# schema2.net
KiCad netlist of a schematic drawn in Altium Designer
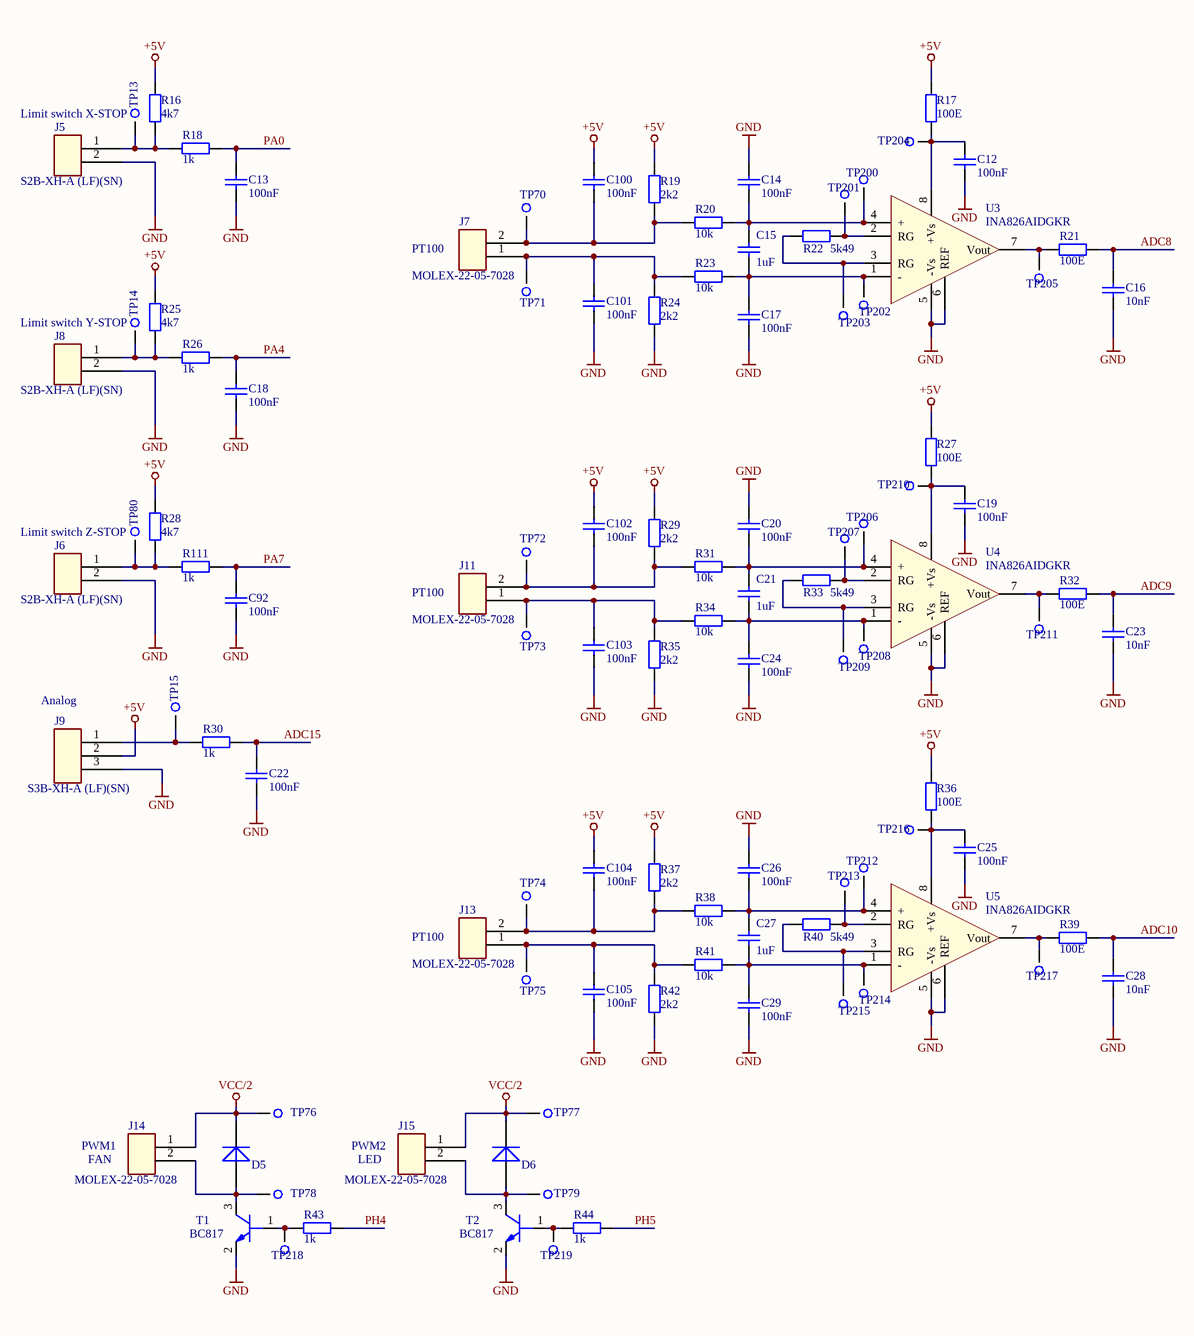
[diagram p0: schema2.SchDoc]

(export (version "E")
  (design (tool "Eeschema 10.0.6"))
  (components
    (comp (ref "C12")
      (value "100nF")
      (footprint "C0603")
      (description "RO X7R 100nF 10% 50V 0603")
      (libsource (lib "Database_Faber") (part "Capacitor"))
    )
    (comp (ref "C13")
      (value "100nF")
      (footprint "C0603")
      (description "RO X7R 100nF 10% 50V 0603")
      (libsource (lib "Database_Faber") (part "Capacitor"))
    )
    (comp (ref "C14")
      (value "100nF")
      (footprint "C0603")
      (description "RO X7R 100nF 10% 50V 0603")
      (libsource (lib "Database_Faber") (part "Capacitor"))
    )
    (comp (ref "C15")
      (value "1uF")
      (footprint "C0603")
      (description "RO X5R 1uF 10% 10V 0603")
      (libsource (lib "Database_Faber") (part "Capacitor"))
    )
    (comp (ref "C16")
      (value "10nF")
      (footprint "C0603")
      (description "RO X7R 10nF 10% 50V 0603")
      (libsource (lib "Database_Faber") (part "Capacitor"))
    )
    (comp (ref "C17")
      (value "100nF")
      (footprint "C0603")
      (description "RO X7R 100nF 10% 50V 0603")
      (libsource (lib "Database_Faber") (part "Capacitor"))
    )
    (comp (ref "C18")
      (value "100nF")
      (footprint "C0603")
      (description "RO X7R 100nF 10% 50V 0603")
      (libsource (lib "Database_Faber") (part "Capacitor"))
    )
    (comp (ref "C19")
      (value "100nF")
      (footprint "C0603")
      (description "RO X7R 100nF 10% 50V 0603")
      (libsource (lib "Database_Faber") (part "Capacitor"))
    )
    (comp (ref "C20")
      (value "100nF")
      (footprint "C0603")
      (description "RO X7R 100nF 10% 50V 0603")
      (libsource (lib "Database_Faber") (part "Capacitor"))
    )
    (comp (ref "C21")
      (value "1uF")
      (footprint "C0603")
      (description "RO X5R 1uF 10% 10V 0603")
      (libsource (lib "Database_Faber") (part "Capacitor"))
    )
    (comp (ref "C22")
      (value "100nF")
      (footprint "C0603")
      (description "RO X7R 100nF 10% 50V 0603")
      (libsource (lib "Database_Faber") (part "Capacitor"))
    )
    (comp (ref "C23")
      (value "10nF")
      (footprint "C0603")
      (description "RO X7R 10nF 10% 50V 0603")
      (libsource (lib "Database_Faber") (part "Capacitor"))
    )
    (comp (ref "C24")
      (value "100nF")
      (footprint "C0603")
      (description "RO X7R 100nF 10% 50V 0603")
      (libsource (lib "Database_Faber") (part "Capacitor"))
    )
    (comp (ref "C25")
      (value "100nF")
      (footprint "C0603")
      (description "RO X7R 100nF 10% 50V 0603")
      (libsource (lib "Database_Faber") (part "Capacitor"))
    )
    (comp (ref "C26")
      (value "100nF")
      (footprint "C0603")
      (description "RO X7R 100nF 10% 50V 0603")
      (libsource (lib "Database_Faber") (part "Capacitor"))
    )
    (comp (ref "C27")
      (value "1uF")
      (footprint "C0603")
      (description "RO X5R 1uF 10% 10V 0603")
      (libsource (lib "Database_Faber") (part "Capacitor"))
    )
    (comp (ref "C28")
      (value "10nF")
      (footprint "C0603")
      (description "RO X7R 10nF 10% 50V 0603")
      (libsource (lib "Database_Faber") (part "Capacitor"))
    )
    (comp (ref "C29")
      (value "100nF")
      (footprint "C0603")
      (description "RO X7R 100nF 10% 50V 0603")
      (libsource (lib "Database_Faber") (part "Capacitor"))
    )
    (comp (ref "C92")
      (value "100nF")
      (footprint "C0603")
      (description "RO X7R 100nF 10% 50V 0603")
      (libsource (lib "Database_Faber") (part "Capacitor"))
    )
    (comp (ref "C100")
      (value "100nF")
      (footprint "C0603")
      (description "RO X7R 100nF 10% 50V 0603")
      (libsource (lib "Database_Faber") (part "Capacitor"))
    )
    (comp (ref "C101")
      (value "100nF")
      (footprint "C0603")
      (description "RO X7R 100nF 10% 50V 0603")
      (libsource (lib "Database_Faber") (part "Capacitor"))
    )
    (comp (ref "C102")
      (value "100nF")
      (footprint "C0603")
      (description "RO X7R 100nF 10% 50V 0603")
      (libsource (lib "Database_Faber") (part "Capacitor"))
    )
    (comp (ref "C103")
      (value "100nF")
      (footprint "C0603")
      (description "RO X7R 100nF 10% 50V 0603")
      (libsource (lib "Database_Faber") (part "Capacitor"))
    )
    (comp (ref "C104")
      (value "100nF")
      (footprint "C0603")
      (description "RO X7R 100nF 10% 50V 0603")
      (libsource (lib "Database_Faber") (part "Capacitor"))
    )
    (comp (ref "C105")
      (value "100nF")
      (footprint "C0603")
      (description "RO X7R 100nF 10% 50V 0603")
      (libsource (lib "Database_Faber") (part "Capacitor"))
    )
    (comp (ref "D5")
      (value "S1G")
      (footprint "DO214AC (SMA)")
      (description "RO DIODE S1G DO-214AC")
      (libsource (lib "Database_Faber") (part "Diode"))
    )
    (comp (ref "D6")
      (value "S1G")
      (footprint "DO214AC (SMA)")
      (description "RO DIODE S1G DO-214AC")
      (libsource (lib "Database_Faber") (part "Diode"))
    )
    (comp (ref "J5")
      (value "S2B-XH-A (LF)(SN)")
      (footprint "S2B-XH-A (LF)(SN)")
      (description "RO CONN PR 2p HKS S2B-XH-A (LF)(SN) JST")
      (fields (field (name "MFG") "JST (JAPAN SOLDERLESS TERMINALS)"))
      (libsource (lib "Database_Faber") (part "HEADER 2"))
    )
    (comp (ref "J6")
      (value "S2B-XH-A (LF)(SN)")
      (footprint "S2B-XH-A (LF)(SN)")
      (description "RO CONN PR 2p HKS S2B-XH-A (LF)(SN) JST")
      (fields (field (name "MFG") "JST (JAPAN SOLDERLESS TERMINALS)"))
      (libsource (lib "Database_Faber") (part "HEADER 2"))
    )
    (comp (ref "J7")
      (value "MOLEX-22-05-7028")
      (footprint "MOLEX-22-05-7028")
      (description "RO CONN PR 2p HKS 22-05-7028 MOLEX")
      (fields (field (name "MFG") "MOLEX"))
      (libsource (lib "") (part "HEADER 2_1"))
    )
    (comp (ref "J8")
      (value "S2B-XH-A (LF)(SN)")
      (footprint "S2B-XH-A (LF)(SN)")
      (description "RO CONN PR 2p HKS S2B-XH-A (LF)(SN) JST")
      (fields (field (name "MFG") "JST (JAPAN SOLDERLESS TERMINALS)"))
      (libsource (lib "Database_Faber") (part "HEADER 2"))
    )
    (comp (ref "J9")
      (value "S3B-XH-A (LF)(SN)")
      (footprint "S3B-XH-A (LF)(SN)")
      (description "RO CONN PR 3p HKS S3B-XH-A (LF)(SN) JST")
      (fields (field (name "MFG") "JST (JAPAN SOLDERLESS TERMINALS)"))
      (libsource (lib "Database_Faber") (part "HEADER 3"))
    )
    (comp (ref "J11")
      (value "MOLEX-22-05-7028")
      (footprint "MOLEX-22-05-7028")
      (description "RO CONN PR 2p HKS 22-05-7028 MOLEX")
      (fields (field (name "MFG") "MOLEX"))
      (libsource (lib "") (part "HEADER 2_1"))
    )
    (comp (ref "J13")
      (value "MOLEX-22-05-7028")
      (footprint "MOLEX-22-05-7028")
      (description "RO CONN PR 2p HKS 22-05-7028 MOLEX")
      (fields (field (name "MFG") "MOLEX"))
      (libsource (lib "") (part "HEADER 2_1"))
    )
    (comp (ref "J14")
      (value "MOLEX-22-05-7028")
      (footprint "MOLEX-22-05-7028")
      (description "RO CONN PR 2p HKS 22-05-7028 MOLEX")
      (fields (field (name "MFG") "MOLEX"))
      (libsource (lib "Database_Faber") (part "HEADER 2"))
    )
    (comp (ref "J15")
      (value "MOLEX-22-05-7028")
      (footprint "MOLEX-22-05-7028")
      (description "RO CONN PR 2p HKS 22-05-7028 MOLEX")
      (fields (field (name "MFG") "MOLEX"))
      (libsource (lib "Database_Faber") (part "HEADER 2"))
    )
    (comp (ref "R16")
      (value "4k7")
      (footprint "R0603")
      (description "RO RES 4k70 1% 0,063W  0603")
      (libsource (lib "") (part "Resistor_2"))
    )
    (comp (ref "R17")
      (value "100E")
      (footprint "R0603")
      (description "RO RES 100E 1% 0,063W  0603")
      (libsource (lib "") (part "Resistor_1"))
    )
    (comp (ref "R18")
      (value "1k")
      (footprint "R0603")
      (description "RO RES 1k0 1% 0,1W  0603")
      (libsource (lib "Database_Faber") (part "Resistor"))
    )
    (comp (ref "R19")
      (value "2k2")
      (footprint "R0603")
      (description "RO RES 2k2 0,1% 0,063W 25ppm 0603")
      (fields (field (name "MFG") "TE CONNECTIVITY / NEOHM"))
      (libsource (lib "") (part "Resistor_1"))
    )
    (comp (ref "R20")
      (value "10k")
      (footprint "R0603")
      (description "RO RES 10k0 1% 0,063W  0603")
      (libsource (lib "Database_Faber") (part "Resistor"))
    )
    (comp (ref "R21")
      (value "100E")
      (footprint "R0603")
      (description "RO RES 100E 1% 0,063W  0603")
      (libsource (lib "Database_Faber") (part "Resistor"))
    )
    (comp (ref "R22")
      (value "5k49")
      (footprint "R0603")
      (description "RO RES 5K49 0,1% 0,063W 25ppm 0603")
      (fields (field (name "MFG") "WELWYN"))
      (libsource (lib "") (part "Resistor_3"))
    )
    (comp (ref "R23")
      (value "10k")
      (footprint "R0603")
      (description "RO RES 10k0 1% 0,063W  0603")
      (libsource (lib "Database_Faber") (part "Resistor"))
    )
    (comp (ref "R24")
      (value "2k2")
      (footprint "R0603")
      (description "RO RES 2k2 0,1% 0,063W 25ppm 0603")
      (fields (field (name "MFG") "TE CONNECTIVITY / NEOHM"))
      (libsource (lib "") (part "Resistor_2"))
    )
    (comp (ref "R25")
      (value "4k7")
      (footprint "R0603")
      (description "RO RES 4k70 1% 0,063W  0603")
      (libsource (lib "") (part "Resistor_2"))
    )
    (comp (ref "R26")
      (value "1k")
      (footprint "R0603")
      (description "RO RES 1k0 1% 0,1W  0603")
      (libsource (lib "Database_Faber") (part "Resistor"))
    )
    (comp (ref "R27")
      (value "100E")
      (footprint "R0603")
      (description "RO RES 100E 1% 0,063W  0603")
      (libsource (lib "") (part "Resistor_1"))
    )
    (comp (ref "R28")
      (value "4k7")
      (footprint "R0603")
      (description "RO RES 4k70 1% 0,063W  0603")
      (libsource (lib "") (part "Resistor_2"))
    )
    (comp (ref "R29")
      (value "2k2")
      (footprint "R0603")
      (description "RO RES 2k2 0,1% 0,063W 25ppm 0603")
      (fields (field (name "MFG") "TE CONNECTIVITY / NEOHM"))
      (libsource (lib "") (part "Resistor_1"))
    )
    (comp (ref "R30")
      (value "1k")
      (footprint "R0603")
      (description "RO RES 1k0 1% 0,1W  0603")
      (libsource (lib "Database_Faber") (part "Resistor"))
    )
    (comp (ref "R31")
      (value "10k")
      (footprint "R0603")
      (description "RO RES 10k0 1% 0,063W  0603")
      (libsource (lib "Database_Faber") (part "Resistor"))
    )
    (comp (ref "R32")
      (value "100E")
      (footprint "R0603")
      (description "RO RES 100E 1% 0,063W  0603")
      (libsource (lib "Database_Faber") (part "Resistor"))
    )
    (comp (ref "R33")
      (value "5k49")
      (footprint "R0603")
      (description "RO RES 5K49 0,1% 0,063W 25ppm 0603")
      (fields (field (name "MFG") "WELWYN"))
      (libsource (lib "") (part "Resistor_3"))
    )
    (comp (ref "R34")
      (value "10k")
      (footprint "R0603")
      (description "RO RES 10k0 1% 0,063W  0603")
      (libsource (lib "Database_Faber") (part "Resistor"))
    )
    (comp (ref "R35")
      (value "2k2")
      (footprint "R0603")
      (description "RO RES 2k2 0,1% 0,063W 25ppm 0603")
      (fields (field (name "MFG") "TE CONNECTIVITY / NEOHM"))
      (libsource (lib "") (part "Resistor_2"))
    )
    (comp (ref "R36")
      (value "100E")
      (footprint "R0603")
      (description "RO RES 100E 1% 0,063W  0603")
      (libsource (lib "") (part "Resistor_1"))
    )
    (comp (ref "R37")
      (value "2k2")
      (footprint "R0603")
      (description "RO RES 2k2 0,1% 0,063W 25ppm 0603")
      (fields (field (name "MFG") "TE CONNECTIVITY / NEOHM"))
      (libsource (lib "") (part "Resistor_1"))
    )
    (comp (ref "R38")
      (value "10k")
      (footprint "R0603")
      (description "RO RES 10k0 1% 0,063W  0603")
      (libsource (lib "Database_Faber") (part "Resistor"))
    )
    (comp (ref "R39")
      (value "100E")
      (footprint "R0603")
      (description "RO RES 100E 1% 0,063W  0603")
      (libsource (lib "Database_Faber") (part "Resistor"))
    )
    (comp (ref "R40")
      (value "5k49")
      (footprint "R0603")
      (description "RO RES 5K49 0,1% 0,063W 25ppm 0603")
      (fields (field (name "MFG") "WELWYN"))
      (libsource (lib "") (part "Resistor_3"))
    )
    (comp (ref "R41")
      (value "10k")
      (footprint "R0603")
      (description "RO RES 10k0 1% 0,063W  0603")
      (libsource (lib "Database_Faber") (part "Resistor"))
    )
    (comp (ref "R42")
      (value "2k2")
      (footprint "R0603")
      (description "RO RES 2k2 0,1% 0,063W 25ppm 0603")
      (fields (field (name "MFG") "TE CONNECTIVITY / NEOHM"))
      (libsource (lib "") (part "Resistor_2"))
    )
    (comp (ref "R43")
      (value "1k")
      (footprint "R0603")
      (description "RO RES 1k0 1% 0,1W  0603")
      (libsource (lib "") (part "Resistor_3"))
    )
    (comp (ref "R44")
      (value "1k")
      (footprint "R0603")
      (description "RO RES 1k0 1% 0,1W  0603")
      (libsource (lib "") (part "Resistor_3"))
    )
    (comp (ref "R111")
      (value "1k")
      (footprint "R0603")
      (description "RO RES 1k0 1% 0,1W  0603")
      (libsource (lib "Database_Faber") (part "Resistor"))
    )
    (comp (ref "T1")
      (value "BC817")
      (footprint "SOT23")
      (description "RO TRANS BC817-25  SOT-23")
      (libsource (lib "Database_Faber") (part "Transistor NPN"))
    )
    (comp (ref "T2")
      (value "BC817")
      (footprint "SOT23")
      (description "RO TRANS BC817-25  SOT-23")
      (libsource (lib "Database_Faber") (part "Transistor NPN"))
    )
    (comp (ref "TP13")
      (value "Testpoint")
      (footprint "Testpoint")
      (libsource (lib "Database_Faber") (part "Testpoint"))
    )
    (comp (ref "TP14")
      (value "Testpoint")
      (footprint "Testpoint")
      (libsource (lib "Database_Faber") (part "Testpoint"))
    )
    (comp (ref "TP15")
      (value "Testpoint")
      (footprint "Testpoint")
      (libsource (lib "Database_Faber") (part "Testpoint"))
    )
    (comp (ref "TP70")
      (value "Testpoint")
      (footprint "Testpoint")
      (libsource (lib "Database_Faber") (part "Testpoint"))
    )
    (comp (ref "TP71")
      (value "Testpoint")
      (footprint "Testpoint")
      (libsource (lib "Database_Faber") (part "Testpoint"))
    )
    (comp (ref "TP72")
      (value "Testpoint")
      (footprint "Testpoint")
      (libsource (lib "Database_Faber") (part "Testpoint"))
    )
    (comp (ref "TP73")
      (value "Testpoint")
      (footprint "Testpoint")
      (libsource (lib "Database_Faber") (part "Testpoint"))
    )
    (comp (ref "TP74")
      (value "Testpoint")
      (footprint "Testpoint")
      (libsource (lib "Database_Faber") (part "Testpoint"))
    )
    (comp (ref "TP75")
      (value "Testpoint")
      (footprint "Testpoint")
      (libsource (lib "Database_Faber") (part "Testpoint"))
    )
    (comp (ref "TP76")
      (value "Testpoint")
      (footprint "Testpoint")
      (libsource (lib "Database_Faber") (part "Testpoint"))
    )
    (comp (ref "TP77")
      (value "Testpoint")
      (footprint "Testpoint")
      (libsource (lib "Database_Faber") (part "Testpoint"))
    )
    (comp (ref "TP78")
      (value "Testpoint")
      (footprint "Testpoint")
      (libsource (lib "Database_Faber") (part "Testpoint"))
    )
    (comp (ref "TP79")
      (value "Testpoint")
      (footprint "Testpoint")
      (libsource (lib "Database_Faber") (part "Testpoint"))
    )
    (comp (ref "TP80")
      (value "Testpoint")
      (footprint "Testpoint")
      (libsource (lib "Database_Faber") (part "Testpoint"))
    )
    (comp (ref "TP200")
      (value "Testpoint 1.6mm")
      (footprint "Testpoint 1.6mm")
      (libsource (lib "Ultimaker") (part "Testpoint 1.6mm"))
    )
    (comp (ref "TP201")
      (value "Testpoint 1.6mm")
      (footprint "Testpoint 1.6mm")
      (libsource (lib "Ultimaker") (part "Testpoint 1.6mm"))
    )
    (comp (ref "TP202")
      (value "Testpoint 1.6mm")
      (footprint "Testpoint 1.6mm")
      (libsource (lib "Ultimaker") (part "Testpoint 1.6mm"))
    )
    (comp (ref "TP203")
      (value "Testpoint 1.6mm")
      (footprint "Testpoint 1.6mm")
      (libsource (lib "Ultimaker") (part "Testpoint 1.6mm"))
    )
    (comp (ref "TP204")
      (value "Testpoint 1.6mm")
      (footprint "Testpoint 1.6mm")
      (libsource (lib "Ultimaker") (part "Testpoint 1.6mm"))
    )
    (comp (ref "TP205")
      (value "Testpoint 1.6mm")
      (footprint "Testpoint 1.6mm")
      (libsource (lib "Ultimaker") (part "Testpoint 1.6mm"))
    )
    (comp (ref "TP206")
      (value "Testpoint 1.6mm")
      (footprint "Testpoint 1.6mm")
      (libsource (lib "Ultimaker") (part "Testpoint 1.6mm"))
    )
    (comp (ref "TP207")
      (value "Testpoint 1.6mm")
      (footprint "Testpoint 1.6mm")
      (libsource (lib "Ultimaker") (part "Testpoint 1.6mm"))
    )
    (comp (ref "TP208")
      (value "Testpoint 1.6mm")
      (footprint "Testpoint 1.6mm")
      (libsource (lib "Ultimaker") (part "Testpoint 1.6mm"))
    )
    (comp (ref "TP209")
      (value "Testpoint 1.6mm")
      (footprint "Testpoint 1.6mm")
      (libsource (lib "Ultimaker") (part "Testpoint 1.6mm"))
    )
    (comp (ref "TP210")
      (value "Testpoint 1.6mm")
      (footprint "Testpoint 1.6mm")
      (libsource (lib "Ultimaker") (part "Testpoint 1.6mm"))
    )
    (comp (ref "TP211")
      (value "Testpoint 1.6mm")
      (footprint "Testpoint 1.6mm")
      (libsource (lib "Ultimaker") (part "Testpoint 1.6mm"))
    )
    (comp (ref "TP212")
      (value "Testpoint 1.6mm")
      (footprint "Testpoint 1.6mm")
      (libsource (lib "Ultimaker") (part "Testpoint 1.6mm"))
    )
    (comp (ref "TP213")
      (value "Testpoint 1.6mm")
      (footprint "Testpoint 1.6mm")
      (libsource (lib "Ultimaker") (part "Testpoint 1.6mm"))
    )
    (comp (ref "TP214")
      (value "Testpoint 1.6mm")
      (footprint "Testpoint 1.6mm")
      (libsource (lib "Ultimaker") (part "Testpoint 1.6mm"))
    )
    (comp (ref "TP215")
      (value "Testpoint 1.6mm")
      (footprint "Testpoint 1.6mm")
      (libsource (lib "Ultimaker") (part "Testpoint 1.6mm"))
    )
    (comp (ref "TP216")
      (value "Testpoint 1.6mm")
      (footprint "Testpoint 1.6mm")
      (libsource (lib "Ultimaker") (part "Testpoint 1.6mm"))
    )
    (comp (ref "TP217")
      (value "Testpoint 1.6mm")
      (footprint "Testpoint 1.6mm")
      (libsource (lib "Ultimaker") (part "Testpoint 1.6mm"))
    )
    (comp (ref "TP218")
      (value "Testpoint 1.6mm")
      (footprint "Testpoint 1.6mm")
      (libsource (lib "Ultimaker") (part "Testpoint 1.6mm"))
    )
    (comp (ref "TP219")
      (value "Testpoint 1.6mm")
      (footprint "Testpoint 1.6mm")
      (libsource (lib "Ultimaker") (part "Testpoint 1.6mm"))
    )
    (comp (ref "U3")
      (value "INA826AIDGKR")
      (footprint "TSOP65P490X110-8N (MSOP8)")
      (description "RO IC INA826AIDGKR MSOP-8 TI")
      (fields (field (name "MFG") "Texas Instruments"))
      (libsource (lib "Database_Faber") (part "INA826AIDGKR"))
    )
    (comp (ref "U4")
      (value "INA826AIDGKR")
      (footprint "TSOP65P490X110-8N (MSOP8)")
      (description "RO IC INA826AIDGKR MSOP-8 TI")
      (fields (field (name "MFG") "Texas Instruments"))
      (libsource (lib "Database_Faber") (part "INA826AIDGKR"))
    )
    (comp (ref "U5")
      (value "INA826AIDGKR")
      (footprint "TSOP65P490X110-8N (MSOP8)")
      (description "RO IC INA826AIDGKR MSOP-8 TI")
      (fields (field (name "MFG") "Texas Instruments"))
      (libsource (lib "Database_Faber") (part "INA826AIDGKR"))
    )
  )
  (nets
    (net (code "1") (name "+5V") (class "Default")
      (node (ref "C100") (pin "2") (pinfunction "2_2") (pintype "passive"))
      (node (ref "C102") (pin "2") (pinfunction "2_2") (pintype "passive"))
      (node (ref "C104") (pin "2") (pinfunction "2_2") (pintype "passive"))
      (node (ref "J9") (pin "2") (pinfunction "2_2") (pintype "passive"))
      (node (ref "R16") (pin "2") (pinfunction "2_2") (pintype "passive"))
      (node (ref "R17") (pin "1") (pinfunction "1_1") (pintype "passive"))
      (node (ref "R19") (pin "1") (pinfunction "1_1") (pintype "passive"))
      (node (ref "R25") (pin "2") (pinfunction "2_2") (pintype "passive"))
      (node (ref "R27") (pin "1") (pinfunction "1_1") (pintype "passive"))
      (node (ref "R28") (pin "2") (pinfunction "2_2") (pintype "passive"))
      (node (ref "R29") (pin "1") (pinfunction "1_1") (pintype "passive"))
      (node (ref "R36") (pin "1") (pinfunction "1_1") (pintype "passive"))
      (node (ref "R37") (pin "1") (pinfunction "1_1") (pintype "passive"))
    )
    (net (code "2") (name "/ADC8") (class "Default")
      (node (ref "C16") (pin "2") (pinfunction "2_2") (pintype "passive"))
      (node (ref "R21") (pin "2") (pinfunction "2_2") (pintype "passive"))
    )
    (net (code "3") (name "/ADC9") (class "Default")
      (node (ref "C23") (pin "2") (pinfunction "2_2") (pintype "passive"))
      (node (ref "R32") (pin "2") (pinfunction "2_2") (pintype "passive"))
    )
    (net (code "4") (name "/ADC10") (class "Default")
      (node (ref "C28") (pin "2") (pinfunction "2_2") (pintype "passive"))
      (node (ref "R39") (pin "2") (pinfunction "2_2") (pintype "passive"))
    )
    (net (code "5") (name "/ADC15") (class "Default")
      (node (ref "C22") (pin "2") (pinfunction "2_2") (pintype "passive"))
      (node (ref "R30") (pin "2") (pinfunction "2_2") (pintype "passive"))
    )
    (net (code "6") (name "/PA0") (class "Default")
      (node (ref "C13") (pin "2") (pinfunction "2_2") (pintype "passive"))
      (node (ref "R18") (pin "2") (pinfunction "2_2") (pintype "passive"))
    )
    (net (code "7") (name "/PA4") (class "Default")
      (node (ref "C18") (pin "2") (pinfunction "2_2") (pintype "passive"))
      (node (ref "R26") (pin "2") (pinfunction "2_2") (pintype "passive"))
    )
    (net (code "8") (name "/PA7") (class "Default")
      (node (ref "C92") (pin "2") (pinfunction "2_2") (pintype "passive"))
      (node (ref "R111") (pin "2") (pinfunction "2_2") (pintype "passive"))
    )
    (net (code "9") (name "/PH4") (class "Default")
      (node (ref "R43") (pin "1") (pinfunction "1_1") (pintype "passive"))
    )
    (net (code "10") (name "/PH5") (class "Default")
      (node (ref "R44") (pin "1") (pinfunction "1_1") (pintype "passive"))
    )
    (net (code "11") (name "GND") (class "Default")
      (node (ref "C101") (pin "1") (pinfunction "1_1") (pintype "passive"))
      (node (ref "C103") (pin "1") (pinfunction "1_1") (pintype "passive"))
      (node (ref "C105") (pin "1") (pinfunction "1_1") (pintype "passive"))
      (node (ref "C12") (pin "1") (pinfunction "1_1") (pintype "passive"))
      (node (ref "C13") (pin "1") (pinfunction "1_1") (pintype "passive"))
      (node (ref "C14") (pin "2") (pinfunction "2_2") (pintype "passive"))
      (node (ref "C16") (pin "1") (pinfunction "1_1") (pintype "passive"))
      (node (ref "C17") (pin "1") (pinfunction "1_1") (pintype "passive"))
      (node (ref "C18") (pin "1") (pinfunction "1_1") (pintype "passive"))
      (node (ref "C19") (pin "1") (pinfunction "1_1") (pintype "passive"))
      (node (ref "C20") (pin "2") (pinfunction "2_2") (pintype "passive"))
      (node (ref "C22") (pin "1") (pinfunction "1_1") (pintype "passive"))
      (node (ref "C23") (pin "1") (pinfunction "1_1") (pintype "passive"))
      (node (ref "C24") (pin "1") (pinfunction "1_1") (pintype "passive"))
      (node (ref "C25") (pin "1") (pinfunction "1_1") (pintype "passive"))
      (node (ref "C26") (pin "2") (pinfunction "2_2") (pintype "passive"))
      (node (ref "C28") (pin "1") (pinfunction "1_1") (pintype "passive"))
      (node (ref "C29") (pin "1") (pinfunction "1_1") (pintype "passive"))
      (node (ref "C92") (pin "1") (pinfunction "1_1") (pintype "passive"))
      (node (ref "J5") (pin "2") (pinfunction "2_2") (pintype "passive"))
      (node (ref "J6") (pin "2") (pinfunction "2_2") (pintype "passive"))
      (node (ref "J8") (pin "2") (pinfunction "2_2") (pintype "passive"))
      (node (ref "J9") (pin "3") (pinfunction "3_3") (pintype "passive"))
      (node (ref "R24") (pin "1") (pinfunction "1_1") (pintype "passive"))
      (node (ref "R35") (pin "1") (pinfunction "1_1") (pintype "passive"))
      (node (ref "R42") (pin "1") (pinfunction "1_1") (pintype "passive"))
      (node (ref "T1") (pin "2") (pinfunction "EMITTER_2") (pintype "passive"))
      (node (ref "T2") (pin "2") (pinfunction "EMITTER_2") (pintype "passive"))
      (node (ref "U3") (pin "5") (pinfunction "-Vs_5") (pintype "passive"))
      (node (ref "U3") (pin "6") (pinfunction "REF_6") (pintype "passive"))
      (node (ref "U4") (pin "5") (pinfunction "-Vs_5") (pintype "passive"))
      (node (ref "U4") (pin "6") (pinfunction "REF_6") (pintype "passive"))
      (node (ref "U5") (pin "5") (pinfunction "-Vs_5") (pintype "passive"))
      (node (ref "U5") (pin "6") (pinfunction "REF_6") (pintype "passive"))
    )
    (net (code "12") (name "Net-(C100-Pad1)") (class "Default")
      (node (ref "C100") (pin "1") (pinfunction "1_1") (pintype "passive"))
      (node (ref "J7") (pin "2") (pinfunction "2_2") (pintype "passive"))
      (node (ref "R19") (pin "2") (pinfunction "2_2") (pintype "passive"))
      (node (ref "R20") (pin "1") (pinfunction "1_1") (pintype "passive"))
      (node (ref "TP70") (pin "1") (pinfunction "1_1") (pintype "passive"))
    )
    (net (code "13") (name "Net-(C101-Pad2)") (class "Default")
      (node (ref "C101") (pin "2") (pinfunction "2_2") (pintype "passive"))
      (node (ref "J7") (pin "1") (pinfunction "1_1") (pintype "passive"))
      (node (ref "R23") (pin "1") (pinfunction "1_1") (pintype "passive"))
      (node (ref "R24") (pin "2") (pinfunction "2_2") (pintype "passive"))
      (node (ref "TP71") (pin "1") (pinfunction "1_1") (pintype "passive"))
    )
    (net (code "14") (name "Net-(C102-Pad1)") (class "Default")
      (node (ref "C102") (pin "1") (pinfunction "1_1") (pintype "passive"))
      (node (ref "J11") (pin "2") (pinfunction "2_2") (pintype "passive"))
      (node (ref "R29") (pin "2") (pinfunction "2_2") (pintype "passive"))
      (node (ref "R31") (pin "1") (pinfunction "1_1") (pintype "passive"))
      (node (ref "TP72") (pin "1") (pinfunction "1_1") (pintype "passive"))
    )
    (net (code "15") (name "Net-(C103-Pad2)") (class "Default")
      (node (ref "C103") (pin "2") (pinfunction "2_2") (pintype "passive"))
      (node (ref "J11") (pin "1") (pinfunction "1_1") (pintype "passive"))
      (node (ref "R34") (pin "1") (pinfunction "1_1") (pintype "passive"))
      (node (ref "R35") (pin "2") (pinfunction "2_2") (pintype "passive"))
      (node (ref "TP73") (pin "1") (pinfunction "1_1") (pintype "passive"))
    )
    (net (code "16") (name "Net-(C104-Pad1)") (class "Default")
      (node (ref "C104") (pin "1") (pinfunction "1_1") (pintype "passive"))
      (node (ref "J13") (pin "2") (pinfunction "2_2") (pintype "passive"))
      (node (ref "R37") (pin "2") (pinfunction "2_2") (pintype "passive"))
      (node (ref "R38") (pin "1") (pinfunction "1_1") (pintype "passive"))
      (node (ref "TP74") (pin "1") (pinfunction "1_1") (pintype "passive"))
    )
    (net (code "17") (name "Net-(C105-Pad2)") (class "Default")
      (node (ref "C105") (pin "2") (pinfunction "2_2") (pintype "passive"))
      (node (ref "J13") (pin "1") (pinfunction "1_1") (pintype "passive"))
      (node (ref "R41") (pin "1") (pinfunction "1_1") (pintype "passive"))
      (node (ref "R42") (pin "2") (pinfunction "2_2") (pintype "passive"))
      (node (ref "TP75") (pin "1") (pinfunction "1_1") (pintype "passive"))
    )
    (net (code "18") (name "Net-(D5-A)") (class "Default")
      (node (ref "D5") (pin "1") (pinfunction "A_1") (pintype "passive"))
      (node (ref "J14") (pin "2") (pinfunction "2_2") (pintype "passive"))
      (node (ref "T1") (pin "3") (pinfunction "COLLECTOR_3") (pintype "passive"))
      (node (ref "TP78") (pin "1") (pinfunction "1_1") (pintype "passive"))
    )
    (net (code "19") (name "Net-(D6-A)") (class "Default")
      (node (ref "D6") (pin "1") (pinfunction "A_1") (pintype "passive"))
      (node (ref "J15") (pin "2") (pinfunction "2_2") (pintype "passive"))
      (node (ref "T2") (pin "3") (pinfunction "COLLECTOR_3") (pintype "passive"))
      (node (ref "TP79") (pin "1") (pinfunction "1_1") (pintype "passive"))
    )
    (net (code "20") (name "Net-(J5-Pad1)") (class "Default")
      (node (ref "J5") (pin "1") (pinfunction "1_1") (pintype "passive"))
      (node (ref "R16") (pin "1") (pinfunction "1_1") (pintype "passive"))
      (node (ref "R18") (pin "1") (pinfunction "1_1") (pintype "passive"))
      (node (ref "TP13") (pin "1") (pinfunction "1_1") (pintype "passive"))
    )
    (net (code "21") (name "Net-(J6-Pad1)") (class "Default")
      (node (ref "J6") (pin "1") (pinfunction "1_1") (pintype "passive"))
      (node (ref "R111") (pin "1") (pinfunction "1_1") (pintype "passive"))
      (node (ref "R28") (pin "1") (pinfunction "1_1") (pintype "passive"))
      (node (ref "TP80") (pin "1") (pinfunction "1_1") (pintype "passive"))
    )
    (net (code "22") (name "Net-(J8-Pad1)") (class "Default")
      (node (ref "J8") (pin "1") (pinfunction "1_1") (pintype "passive"))
      (node (ref "R25") (pin "1") (pinfunction "1_1") (pintype "passive"))
      (node (ref "R26") (pin "1") (pinfunction "1_1") (pintype "passive"))
      (node (ref "TP14") (pin "1") (pinfunction "1_1") (pintype "passive"))
    )
    (net (code "23") (name "Net-(J9-Pad1)") (class "Default")
      (node (ref "J9") (pin "1") (pinfunction "1_1") (pintype "passive"))
      (node (ref "R30") (pin "1") (pinfunction "1_1") (pintype "passive"))
      (node (ref "TP15") (pin "1") (pinfunction "1_1") (pintype "passive"))
    )
    (net (code "24") (name "Net-(R22-Pad1)") (class "Default")
      (node (ref "R22") (pin "1") (pinfunction "1_1") (pintype "passive"))
      (node (ref "TP201") (pin "1") (pinfunction "1_1") (pintype "passive"))
      (node (ref "U3") (pin "2") (pinfunction "RG_2") (pintype "passive"))
    )
    (net (code "25") (name "Net-(R22-Pad2)") (class "Default")
      (node (ref "R22") (pin "2") (pinfunction "2_2") (pintype "passive"))
      (node (ref "TP203") (pin "1") (pinfunction "1_1") (pintype "passive"))
      (node (ref "U3") (pin "3") (pinfunction "RG_3") (pintype "passive"))
    )
    (net (code "26") (name "Net-(R33-Pad1)") (class "Default")
      (node (ref "R33") (pin "1") (pinfunction "1_1") (pintype "passive"))
      (node (ref "TP207") (pin "1") (pinfunction "1_1") (pintype "passive"))
      (node (ref "U4") (pin "2") (pinfunction "RG_2") (pintype "passive"))
    )
    (net (code "27") (name "Net-(R33-Pad2)") (class "Default")
      (node (ref "R33") (pin "2") (pinfunction "2_2") (pintype "passive"))
      (node (ref "TP209") (pin "1") (pinfunction "1_1") (pintype "passive"))
      (node (ref "U4") (pin "3") (pinfunction "RG_3") (pintype "passive"))
    )
    (net (code "28") (name "Net-(R40-Pad1)") (class "Default")
      (node (ref "R40") (pin "1") (pinfunction "1_1") (pintype "passive"))
      (node (ref "TP213") (pin "1") (pinfunction "1_1") (pintype "passive"))
      (node (ref "U5") (pin "2") (pinfunction "RG_2") (pintype "passive"))
    )
    (net (code "29") (name "Net-(R40-Pad2)") (class "Default")
      (node (ref "R40") (pin "2") (pinfunction "2_2") (pintype "passive"))
      (node (ref "TP215") (pin "1") (pinfunction "1_1") (pintype "passive"))
      (node (ref "U5") (pin "3") (pinfunction "RG_3") (pintype "passive"))
    )
    (net (code "30") (name "Net-(T1-BASE)") (class "Default")
      (node (ref "R43") (pin "2") (pinfunction "2_2") (pintype "passive"))
      (node (ref "T1") (pin "1") (pinfunction "BASE_1") (pintype "passive"))
      (node (ref "TP218") (pin "1") (pinfunction "1_1") (pintype "passive"))
    )
    (net (code "31") (name "Net-(T2-BASE)") (class "Default")
      (node (ref "R44") (pin "2") (pinfunction "2_2") (pintype "passive"))
      (node (ref "T2") (pin "1") (pinfunction "BASE_1") (pintype "passive"))
      (node (ref "TP219") (pin "1") (pinfunction "1_1") (pintype "passive"))
    )
    (net (code "32") (name "Net-(U3-+)") (class "Default")
      (node (ref "C14") (pin "1") (pinfunction "1_1") (pintype "passive"))
      (node (ref "C15") (pin "2") (pinfunction "2_2") (pintype "passive"))
      (node (ref "R20") (pin "2") (pinfunction "2_2") (pintype "passive"))
      (node (ref "TP200") (pin "1") (pinfunction "1_1") (pintype "passive"))
      (node (ref "U3") (pin "4") (pinfunction "+_4") (pintype "passive"))
    )
    (net (code "33") (name "Net-(U3-+Vs)") (class "Default")
      (node (ref "C12") (pin "2") (pinfunction "2_2") (pintype "passive"))
      (node (ref "R17") (pin "2") (pinfunction "2_2") (pintype "passive"))
      (node (ref "TP204") (pin "1") (pinfunction "1_1") (pintype "passive"))
      (node (ref "U3") (pin "8") (pinfunction "+Vs_8") (pintype "passive"))
    )
    (net (code "34") (name "Net-(U3--)") (class "Default")
      (node (ref "C15") (pin "1") (pinfunction "1_1") (pintype "passive"))
      (node (ref "C17") (pin "2") (pinfunction "2_2") (pintype "passive"))
      (node (ref "R23") (pin "2") (pinfunction "2_2") (pintype "passive"))
      (node (ref "TP202") (pin "1") (pinfunction "1_1") (pintype "passive"))
      (node (ref "U3") (pin "1") (pinfunction "-_1") (pintype "passive"))
    )
    (net (code "35") (name "Net-(U3-Vout)") (class "Default")
      (node (ref "R21") (pin "1") (pinfunction "1_1") (pintype "passive"))
      (node (ref "TP205") (pin "1") (pinfunction "1_1") (pintype "passive"))
      (node (ref "U3") (pin "7") (pinfunction "Vout_7") (pintype "passive"))
    )
    (net (code "36") (name "Net-(U4-+)") (class "Default")
      (node (ref "C20") (pin "1") (pinfunction "1_1") (pintype "passive"))
      (node (ref "C21") (pin "2") (pinfunction "2_2") (pintype "passive"))
      (node (ref "R31") (pin "2") (pinfunction "2_2") (pintype "passive"))
      (node (ref "TP206") (pin "1") (pinfunction "1_1") (pintype "passive"))
      (node (ref "U4") (pin "4") (pinfunction "+_4") (pintype "passive"))
    )
    (net (code "37") (name "Net-(U4-+Vs)") (class "Default")
      (node (ref "C19") (pin "2") (pinfunction "2_2") (pintype "passive"))
      (node (ref "R27") (pin "2") (pinfunction "2_2") (pintype "passive"))
      (node (ref "TP210") (pin "1") (pinfunction "1_1") (pintype "passive"))
      (node (ref "U4") (pin "8") (pinfunction "+Vs_8") (pintype "passive"))
    )
    (net (code "38") (name "Net-(U4--)") (class "Default")
      (node (ref "C21") (pin "1") (pinfunction "1_1") (pintype "passive"))
      (node (ref "C24") (pin "2") (pinfunction "2_2") (pintype "passive"))
      (node (ref "R34") (pin "2") (pinfunction "2_2") (pintype "passive"))
      (node (ref "TP208") (pin "1") (pinfunction "1_1") (pintype "passive"))
      (node (ref "U4") (pin "1") (pinfunction "-_1") (pintype "passive"))
    )
    (net (code "39") (name "Net-(U4-Vout)") (class "Default")
      (node (ref "R32") (pin "1") (pinfunction "1_1") (pintype "passive"))
      (node (ref "TP211") (pin "1") (pinfunction "1_1") (pintype "passive"))
      (node (ref "U4") (pin "7") (pinfunction "Vout_7") (pintype "passive"))
    )
    (net (code "40") (name "Net-(U5-+)") (class "Default")
      (node (ref "C26") (pin "1") (pinfunction "1_1") (pintype "passive"))
      (node (ref "C27") (pin "2") (pinfunction "2_2") (pintype "passive"))
      (node (ref "R38") (pin "2") (pinfunction "2_2") (pintype "passive"))
      (node (ref "TP212") (pin "1") (pinfunction "1_1") (pintype "passive"))
      (node (ref "U5") (pin "4") (pinfunction "+_4") (pintype "passive"))
    )
    (net (code "41") (name "Net-(U5-+Vs)") (class "Default")
      (node (ref "C25") (pin "2") (pinfunction "2_2") (pintype "passive"))
      (node (ref "R36") (pin "2") (pinfunction "2_2") (pintype "passive"))
      (node (ref "TP216") (pin "1") (pinfunction "1_1") (pintype "passive"))
      (node (ref "U5") (pin "8") (pinfunction "+Vs_8") (pintype "passive"))
    )
    (net (code "42") (name "Net-(U5--)") (class "Default")
      (node (ref "C27") (pin "1") (pinfunction "1_1") (pintype "passive"))
      (node (ref "C29") (pin "2") (pinfunction "2_2") (pintype "passive"))
      (node (ref "R41") (pin "2") (pinfunction "2_2") (pintype "passive"))
      (node (ref "TP214") (pin "1") (pinfunction "1_1") (pintype "passive"))
      (node (ref "U5") (pin "1") (pinfunction "-_1") (pintype "passive"))
    )
    (net (code "43") (name "Net-(U5-Vout)") (class "Default")
      (node (ref "R39") (pin "1") (pinfunction "1_1") (pintype "passive"))
      (node (ref "TP217") (pin "1") (pinfunction "1_1") (pintype "passive"))
      (node (ref "U5") (pin "7") (pinfunction "Vout_7") (pintype "passive"))
    )
    (net (code "44") (name "VCC{slash}2") (class "Default")
      (node (ref "D5") (pin "2") (pinfunction "K_2") (pintype "passive"))
      (node (ref "D6") (pin "2") (pinfunction "K_2") (pintype "passive"))
      (node (ref "J14") (pin "1") (pinfunction "1_1") (pintype "passive"))
      (node (ref "J15") (pin "1") (pinfunction "1_1") (pintype "passive"))
      (node (ref "TP76") (pin "1") (pinfunction "1_1") (pintype "passive"))
      (node (ref "TP77") (pin "1") (pinfunction "1_1") (pintype "passive"))
    )
  )
)
